# mediacontroller_sender.net
KiCad netlist of a schematic drawn in EasyEDA
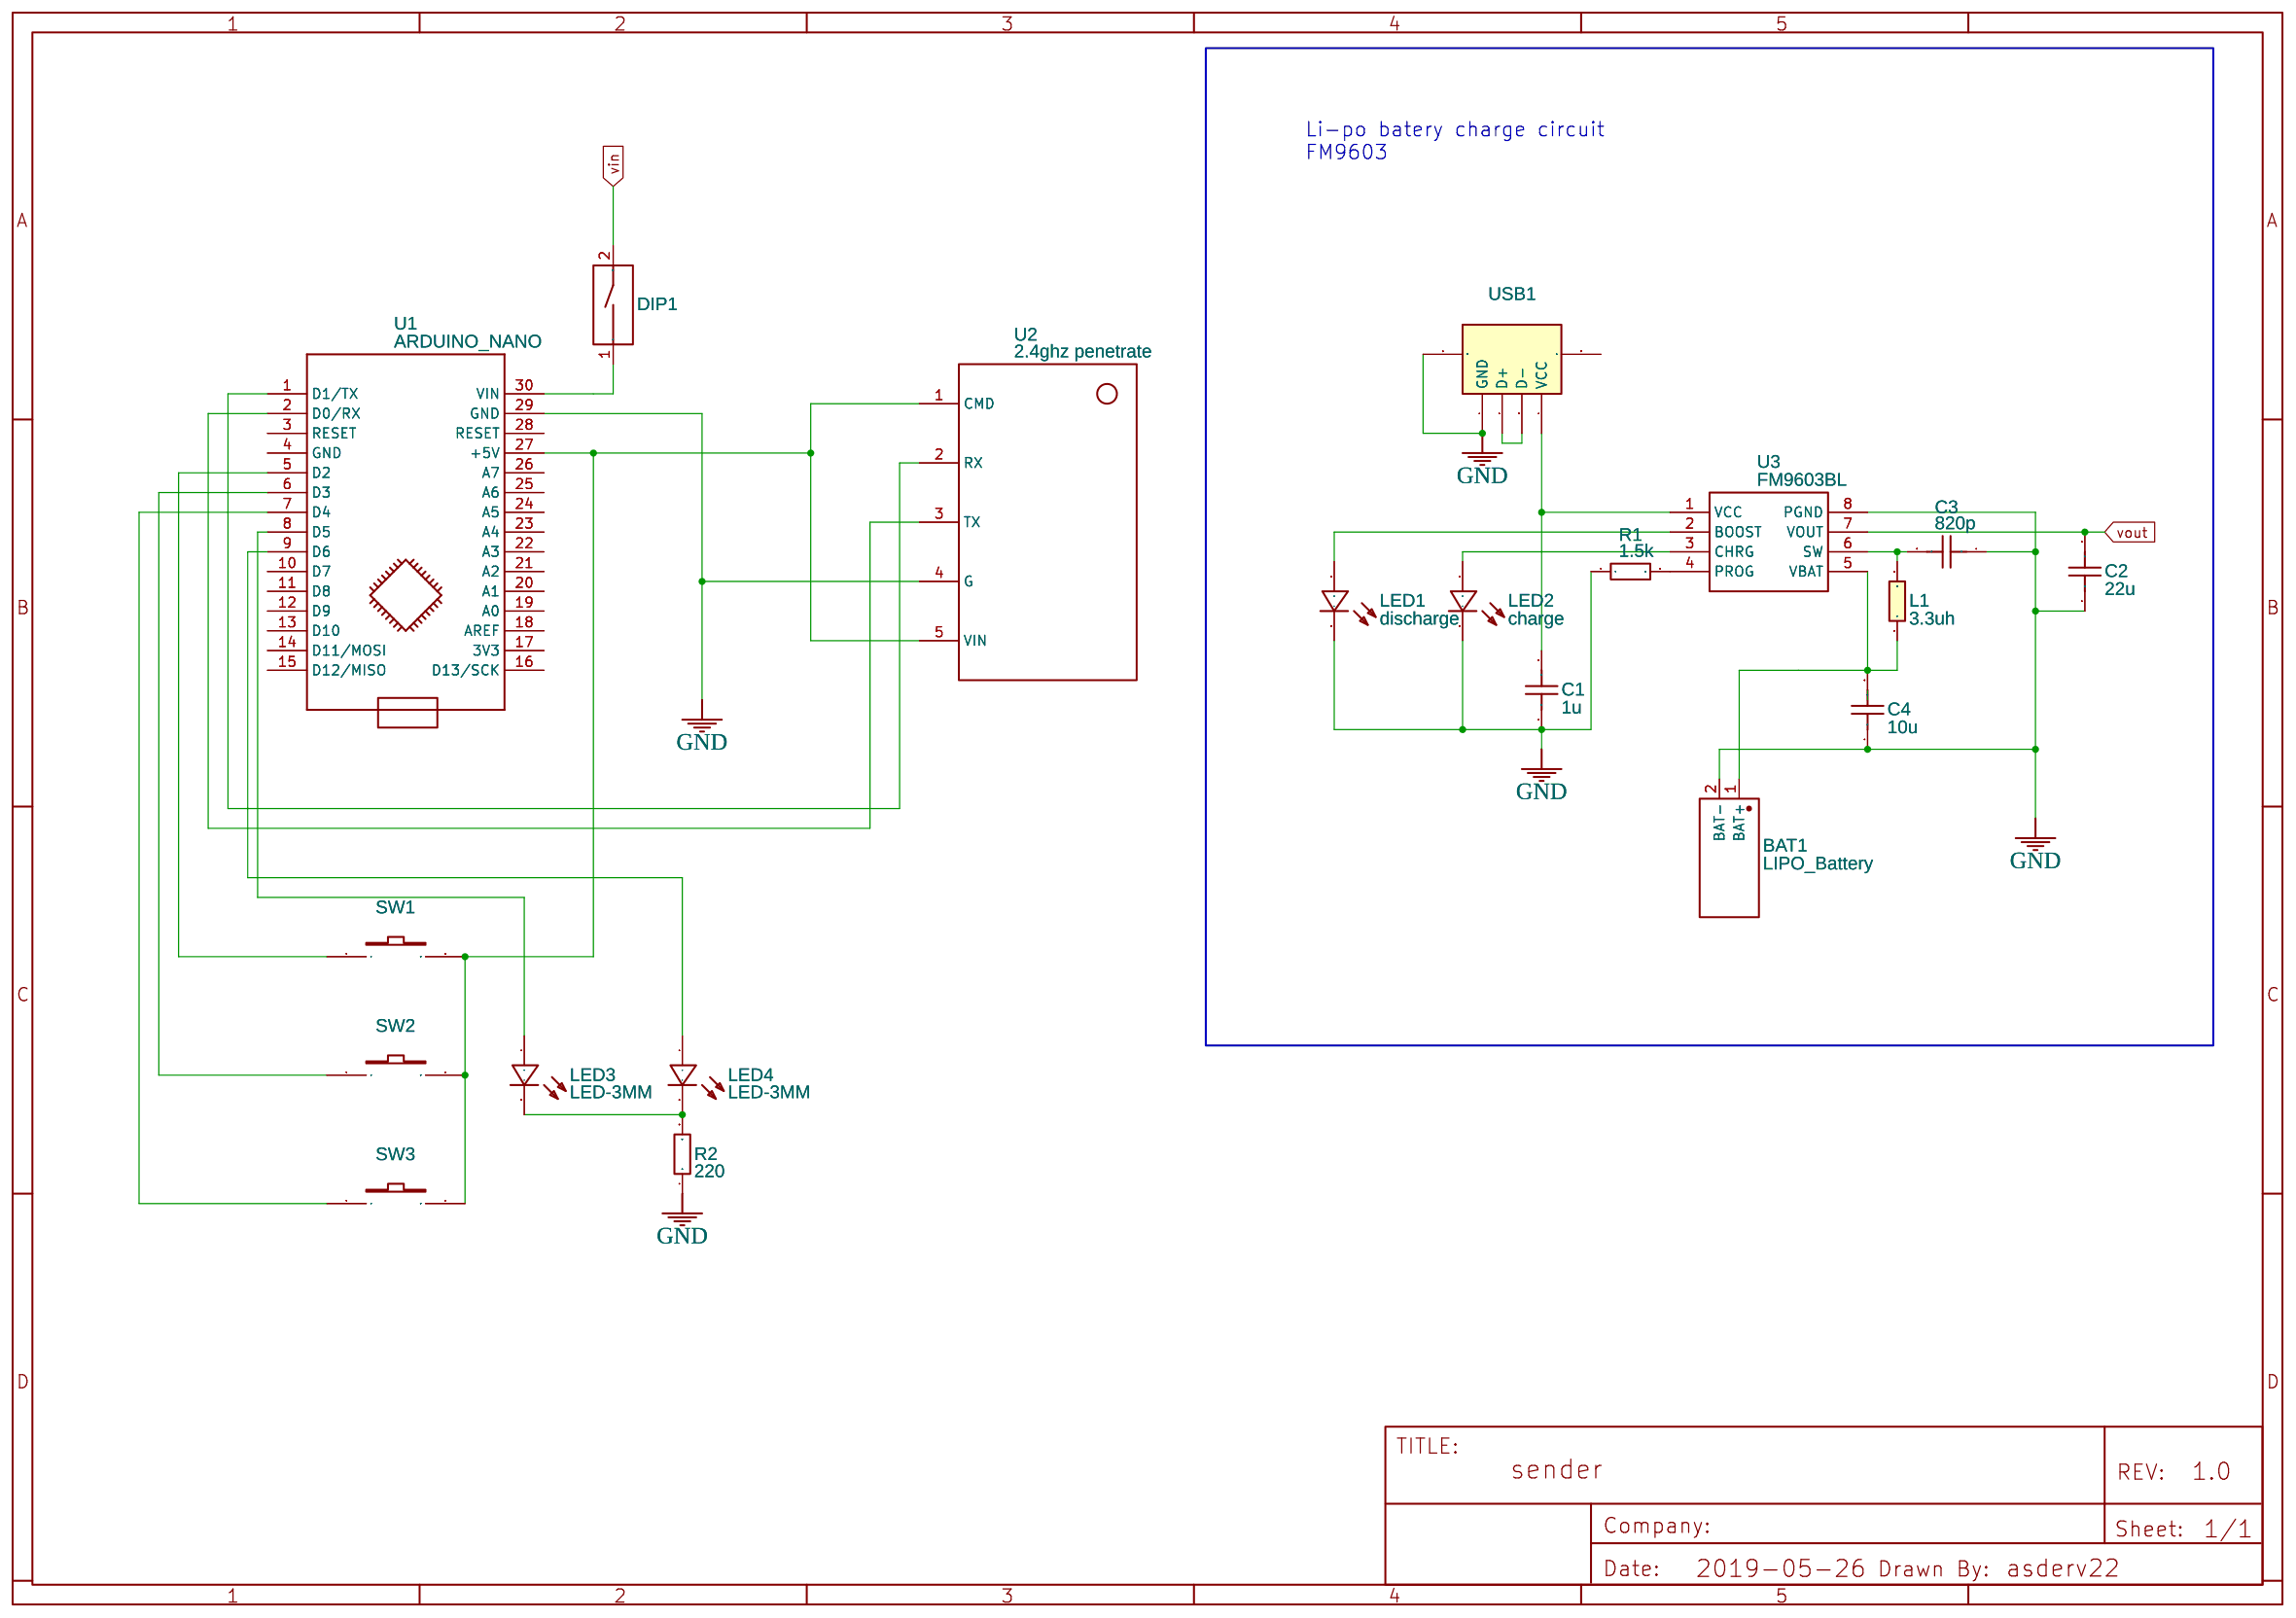
[diagram p0: schematic sheet]

(export (version "E")
  (design (tool "Eeschema 10.0.6"))
  (components
    (comp (ref "BAT1") (value "LIPO_Battery") (libsource (lib "") (part "Unknown_885_400")))
    (comp (ref "C1")
      (value "1u")
      (fields (field (name "BOM_Manufacturer Part") "?"))
      (libsource (lib "") (part "Cap_RAD-0.1_US"))
    )
    (comp (ref "C2")
      (value "22u")
      (fields (field (name "BOM_Manufacturer Part") "?"))
      (libsource (lib "") (part "Cap_RAD-0.1_US"))
    )
    (comp (ref "C3")
      (value "820p")
      (fields (field (name "BOM_Manufacturer Part") "?"))
      (libsource (lib "") (part "Cap_RAD-0.1_US_1"))
    )
    (comp (ref "C4")
      (value "10u")
      (fields (field (name "BOM_Manufacturer Part") "?"))
      (libsource (lib "") (part "Cap_RAD-0.1_US"))
    )
    (comp (ref "DIP1")
      (value "VDG/S-01L blue")
      (fields (field (name "BOM_Supplier Part") "C47086"))
      (libsource (lib "") (part "Unknown_305_150"))
    )
    (comp (ref "L1")
      (value "3.3uh")
      (fields (field (name "BOM_Manufacturer Part") "?"))
      (libsource (lib "") (part "Inductor_AXIAL-0.4_EU"))
    )
    (comp (ref "LED1")
      (value "discharge")
      (fields
        (field (name "BOM_Manufacturer Part") "204-10SURD/S530-A3")
        (field (name "BOM_Supplier Part") "C99772")
      )
      (libsource (lib "") (part "Unknown_670_300"))
    )
    (comp (ref "LED2")
      (value "charge")
      (fields
        (field (name "BOM_Manufacturer Part") "204-10SURD/S530-A3")
        (field (name "BOM_Supplier Part") "C99772")
      )
      (libsource (lib "") (part "Unknown_735_300"))
    )
    (comp (ref "LED3")
      (value "LED-3MM")
      (fields
        (field (name "BOM_Manufacturer Part") "204-10SURD/S530-A3")
        (field (name "BOM_Supplier Part") "C99772")
      )
      (libsource (lib "") (part "Unknown_260_540"))
    )
    (comp (ref "LED4")
      (value "LED-3MM")
      (fields
        (field (name "BOM_Manufacturer Part") "204-10SURD/S530-A3")
        (field (name "BOM_Supplier Part") "C99772")
      )
      (libsource (lib "") (part "Unknown_340_540"))
    )
    (comp (ref "R1")
      (value "1.5k")
      (fields (field (name "BOM_Manufacturer Part") "?"))
      (libsource (lib "") (part "Res_AXIAL-0.3(1/8W)_EU"))
    )
    (comp (ref "R2")
      (value "220")
      (fields (field (name "BOM_Manufacturer Part") "?"))
      (libsource (lib "") (part "Res_AXIAL-0.3(1/8W)_EU_1"))
    )
    (comp (ref "SW1")
      (value "EVQ22705R")
      (fields (field (name "BOM_Supplier Part") "C79156"))
      (libsource (lib "") (part "Unknown_195_480"))
    )
    (comp (ref "SW2")
      (value "EVQ22705R")
      (fields (field (name "BOM_Supplier Part") "C79156"))
      (libsource (lib "") (part "Unknown_195_540"))
    )
    (comp (ref "SW3")
      (value "EVQ22705R")
      (fields (field (name "BOM_Supplier Part") "C79156"))
      (libsource (lib "") (part "Unknown_195_605"))
    )
    (comp (ref "U1")
      (value "ARDUINO_NANO")
      (fields (field (name "BOM_Manufacturer Part") "?"))
      (libsource (lib "") (part "Unknown_200_270"))
    )
    (comp (ref "U2")
      (value "2.4ghz penetrate")
      (fields (field (name "BOM_Manufacturer Part") "?"))
      (libsource (lib "") (part "Unknown_530_260"))
    )
    (comp (ref "U3")
      (value "FM9603BL")
      (fields (field (name "BOM_Supplier Part") "undefined"))
      (libsource (lib "") (part "Unknown_890_270"))
    )
    (comp (ref "USB1")
      (value "USBConnector AF180degree13.1Straight iron Vinyl")
      (fields (field (name "BOM_Supplier Part") "C65604"))
      (libsource (lib "") (part "Unknown_760_190"))
    )
  )
  (nets
    (net (code "1") (name "GND") (class "Default")
      (node (ref "BAT1") (pin "2") (pinfunction "BAT-_2") (pintype "unspecified"))
      (node (ref "C1") (pin "1") (pinfunction "1_1") (pintype "unspecified"))
      (node (ref "C2") (pin "1") (pinfunction "1_1") (pintype "unspecified"))
      (node (ref "C3") (pin "1") (pinfunction "1_1") (pintype "unspecified"))
      (node (ref "C4") (pin "1") (pinfunction "1_1") (pintype "unspecified"))
      (node (ref "LED1") (pin "2") (pinfunction "-_2") (pintype "unspecified"))
      (node (ref "LED2") (pin "2") (pinfunction "-_2") (pintype "unspecified"))
      (node (ref "R1") (pin "1") (pinfunction "1_1") (pintype "unspecified"))
      (node (ref "R2") (pin "1") (pinfunction "1_1") (pintype "unspecified"))
      (node (ref "U1") (pin "29") (pinfunction "GND_29") (pintype "unspecified"))
      (node (ref "U2") (pin "4") (pinfunction "G_4") (pintype "unspecified"))
      (node (ref "U3") (pin "8") (pinfunction "PGND_8") (pintype "unspecified"))
      (node (ref "USB1") (pin "0") (pinfunction "0_0") (pintype "unspecified"))
      (node (ref "USB1") (pin "4") (pinfunction "GND_4") (pintype "input"))
    )
    (net (code "2") (name "Net-(BAT1-BAT+)") (class "Default")
      (node (ref "BAT1") (pin "1") (pinfunction "BAT+_1") (pintype "unspecified"))
      (node (ref "C4") (pin "2") (pinfunction "2_2") (pintype "unspecified"))
      (node (ref "L1") (pin "1") (pinfunction "1_1") (pintype "unspecified"))
      (node (ref "U3") (pin "5") (pinfunction "VBAT_5") (pintype "unspecified"))
    )
    (net (code "3") (name "Net-(LED1-+)") (class "Default")
      (node (ref "LED1") (pin "1") (pinfunction "+_1") (pintype "unspecified"))
      (node (ref "U3") (pin "2") (pinfunction "BOOST_2") (pintype "unspecified"))
    )
    (net (code "4") (name "Net-(LED2-+)") (class "Default")
      (node (ref "LED2") (pin "1") (pinfunction "+_1") (pintype "unspecified"))
      (node (ref "U3") (pin "3") (pinfunction "CHRG_3") (pintype "unspecified"))
    )
    (net (code "5") (name "Net-(LED3-+)") (class "Default")
      (node (ref "LED3") (pin "1") (pinfunction "+_1") (pintype "unspecified"))
      (node (ref "U1") (pin "8") (pinfunction "D5_8") (pintype "unspecified"))
    )
    (net (code "6") (name "Net-(LED3--)") (class "Default")
      (node (ref "LED3") (pin "2") (pinfunction "-_2") (pintype "unspecified"))
      (node (ref "LED4") (pin "2") (pinfunction "-_2") (pintype "unspecified"))
      (node (ref "R2") (pin "2") (pinfunction "2_2") (pintype "unspecified"))
    )
    (net (code "7") (name "Net-(LED4-+)") (class "Default")
      (node (ref "LED4") (pin "1") (pinfunction "+_1") (pintype "unspecified"))
      (node (ref "U1") (pin "9") (pinfunction "D6_9") (pintype "unspecified"))
    )
    (net (code "8") (name "Net-(U1-+5V)") (class "Default")
      (node (ref "SW1") (pin "2") (pinfunction "2_2") (pintype "input"))
      (node (ref "SW2") (pin "2") (pinfunction "2_2") (pintype "input"))
      (node (ref "SW3") (pin "2") (pinfunction "2_2") (pintype "input"))
      (node (ref "U1") (pin "27") (pinfunction "+5V_27") (pintype "unspecified"))
      (node (ref "U2") (pin "1") (pinfunction "CMD_1") (pintype "unspecified"))
      (node (ref "U2") (pin "5") (pinfunction "VIN_5") (pintype "unspecified"))
    )
    (net (code "9") (name "Net-(U1-D0{slash}RX)") (class "Default")
      (node (ref "U1") (pin "2") (pinfunction "D0/RX_2") (pintype "unspecified"))
      (node (ref "U2") (pin "3") (pinfunction "TX_3") (pintype "unspecified"))
    )
    (net (code "10") (name "Net-(U1-D1{slash}TX)") (class "Default")
      (node (ref "U1") (pin "1") (pinfunction "D1/TX_1") (pintype "unspecified"))
      (node (ref "U2") (pin "2") (pinfunction "RX_2") (pintype "unspecified"))
    )
    (net (code "11") (name "Net-(U1-D2)") (class "Default")
      (node (ref "SW1") (pin "1") (pinfunction "1_1") (pintype "input"))
      (node (ref "U1") (pin "5") (pinfunction "D2_5") (pintype "unspecified"))
    )
    (net (code "12") (name "Net-(U1-D3)") (class "Default")
      (node (ref "SW2") (pin "1") (pinfunction "1_1") (pintype "input"))
      (node (ref "U1") (pin "6") (pinfunction "D3_6") (pintype "unspecified"))
    )
    (net (code "13") (name "Net-(U1-D4)") (class "Default")
      (node (ref "SW3") (pin "1") (pinfunction "1_1") (pintype "input"))
      (node (ref "U1") (pin "7") (pinfunction "D4_7") (pintype "unspecified"))
    )
    (net (code "14") (name "Net-(U1-VIN)") (class "Default")
      (node (ref "DIP1") (pin "1") (pinfunction "1_1") (pintype "unspecified"))
      (node (ref "U1") (pin "30") (pinfunction "VIN_30") (pintype "unspecified"))
    )
    (net (code "15") (name "Net-(U3-PROG)") (class "Default")
      (node (ref "R1") (pin "2") (pinfunction "2_2") (pintype "unspecified"))
      (node (ref "U3") (pin "4") (pinfunction "PROG_4") (pintype "unspecified"))
    )
    (net (code "16") (name "Net-(U3-SW)") (class "Default")
      (node (ref "C3") (pin "2") (pinfunction "2_2") (pintype "unspecified"))
      (node (ref "L1") (pin "2") (pinfunction "2_2") (pintype "unspecified"))
      (node (ref "U3") (pin "6") (pinfunction "SW_6") (pintype "unspecified"))
    )
    (net (code "17") (name "Net-(U3-VCC)") (class "Default")
      (node (ref "C1") (pin "2") (pinfunction "2_2") (pintype "unspecified"))
      (node (ref "U3") (pin "1") (pinfunction "VCC_1") (pintype "unspecified"))
      (node (ref "USB1") (pin "1") (pinfunction "VCC_1") (pintype "input"))
    )
    (net (code "18") (name "Net-(USB1-D+)") (class "Default")
      (node (ref "USB1") (pin "2") (pinfunction "D-_2") (pintype "input"))
      (node (ref "USB1") (pin "3") (pinfunction "D+_3") (pintype "input"))
    )
    (net (code "19") (name "unconnected-(U1-3V3-Pad17)") (class "Default")
      (node (ref "U1") (pin "17") (pinfunction "3V3_17") (pintype "unspecified"))
    )
    (net (code "20") (name "unconnected-(U1-A0-Pad19)") (class "Default")
      (node (ref "U1") (pin "19") (pinfunction "A0_19") (pintype "unspecified"))
    )
    (net (code "21") (name "unconnected-(U1-A1-Pad20)") (class "Default")
      (node (ref "U1") (pin "20") (pinfunction "A1_20") (pintype "unspecified"))
    )
    (net (code "22") (name "unconnected-(U1-A2-Pad21)") (class "Default")
      (node (ref "U1") (pin "21") (pinfunction "A2_21") (pintype "unspecified"))
    )
    (net (code "23") (name "unconnected-(U1-A3-Pad22)") (class "Default")
      (node (ref "U1") (pin "22") (pinfunction "A3_22") (pintype "unspecified"))
    )
    (net (code "24") (name "unconnected-(U1-A4-Pad23)") (class "Default")
      (node (ref "U1") (pin "23") (pinfunction "A4_23") (pintype "unspecified"))
    )
    (net (code "25") (name "unconnected-(U1-A5-Pad24)") (class "Default")
      (node (ref "U1") (pin "24") (pinfunction "A5_24") (pintype "unspecified"))
    )
    (net (code "26") (name "unconnected-(U1-A6-Pad25)") (class "Default")
      (node (ref "U1") (pin "25") (pinfunction "A6_25") (pintype "unspecified"))
    )
    (net (code "27") (name "unconnected-(U1-A7-Pad26)") (class "Default")
      (node (ref "U1") (pin "26") (pinfunction "A7_26") (pintype "unspecified"))
    )
    (net (code "28") (name "unconnected-(U1-AREF-Pad18)") (class "Default")
      (node (ref "U1") (pin "18") (pinfunction "AREF_18") (pintype "unspecified"))
    )
    (net (code "29") (name "unconnected-(U1-D7-Pad10)") (class "Default")
      (node (ref "U1") (pin "10") (pinfunction "D7_10") (pintype "unspecified"))
    )
    (net (code "30") (name "unconnected-(U1-D8-Pad11)") (class "Default")
      (node (ref "U1") (pin "11") (pinfunction "D8_11") (pintype "unspecified"))
    )
    (net (code "31") (name "unconnected-(U1-D9-Pad12)") (class "Default")
      (node (ref "U1") (pin "12") (pinfunction "D9_12") (pintype "unspecified"))
    )
    (net (code "32") (name "unconnected-(U1-D10-Pad13)") (class "Default")
      (node (ref "U1") (pin "13") (pinfunction "D10_13") (pintype "unspecified"))
    )
    (net (code "33") (name "unconnected-(U1-D11{slash}MOSI-Pad14)") (class "Default")
      (node (ref "U1") (pin "14") (pinfunction "D11/MOSI_14") (pintype "unspecified"))
    )
    (net (code "34") (name "unconnected-(U1-D12{slash}MISO-Pad15)") (class "Default")
      (node (ref "U1") (pin "15") (pinfunction "D12/MISO_15") (pintype "unspecified"))
    )
    (net (code "35") (name "unconnected-(U1-D13{slash}SCK-Pad16)") (class "Default")
      (node (ref "U1") (pin "16") (pinfunction "D13/SCK_16") (pintype "unspecified"))
    )
    (net (code "36") (name "unconnected-(U1-GND-Pad4)") (class "Default")
      (node (ref "U1") (pin "4") (pinfunction "GND_4") (pintype "unspecified"))
    )
    (net (code "37") (name "unconnected-(U1-RESET-Pad3)") (class "Default")
      (node (ref "U1") (pin "3") (pinfunction "RESET_3") (pintype "unspecified"))
    )
    (net (code "38") (name "unconnected-(U1-RESET-Pad28)") (class "Default")
      (node (ref "U1") (pin "28") (pinfunction "RESET_28") (pintype "unspecified"))
    )
    (net (code "39") (name "unconnected-(USB1-Pad0)") (class "Default")
      (node (ref "USB1") (pin "0") (pinfunction "0_0") (pintype "unspecified"))
    )
    (net (code "40") (name "vin") (class "Default")
      (node (ref "DIP1") (pin "2") (pinfunction "2_2") (pintype "unspecified"))
    )
    (net (code "41") (name "vout") (class "Default")
      (node (ref "C2") (pin "2") (pinfunction "2_2") (pintype "unspecified"))
      (node (ref "U3") (pin "7") (pinfunction "VOUT_7") (pintype "unspecified"))
    )
  )
)
